# Lipo_Saver.net
KiCad netlist of a schematic drawn in Altium Designer
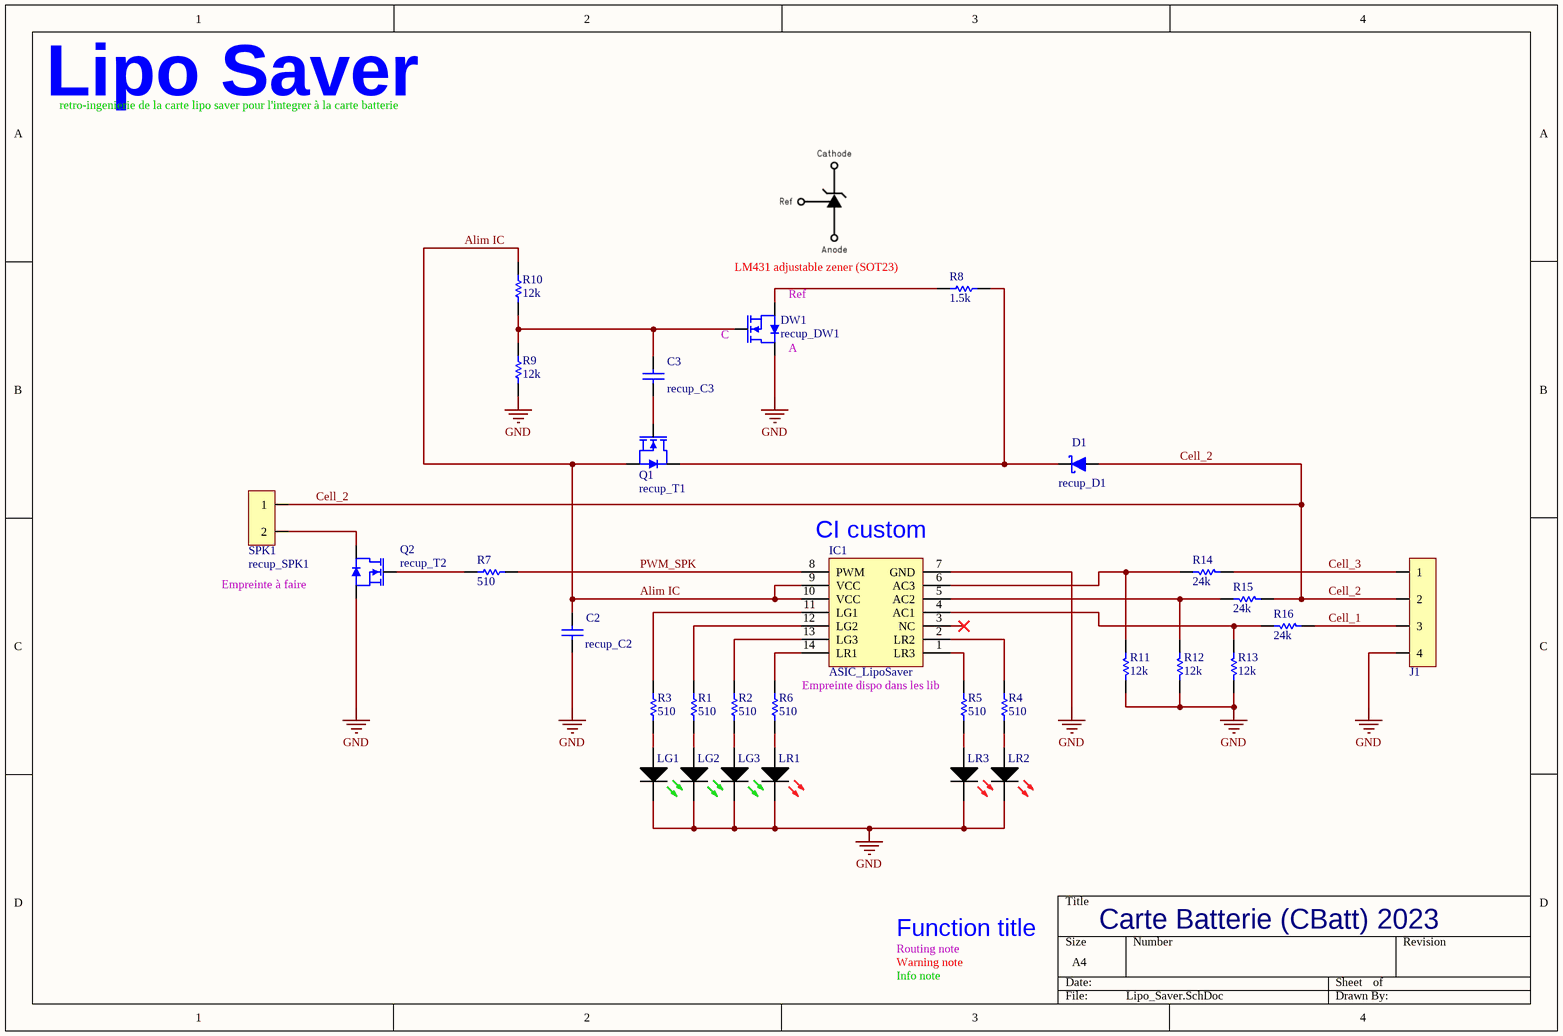
[diagram p0: Lipo_Saver.SchDoc]

(export (version "E")
  (design (tool "Eeschema 10.0.6"))
  (components
    (comp (ref "C2")
      (value "recup_C2")
      (footprint "WCAP-CSGP_0805, 2x1.25x1.25")
      (description "CAP CER 1uF 50V X7R 0805")
      (fields
        (field (name "MANUFACTURER") "Wurth Elektronik")
        (field (name "MANUFACTURER PART NUMBER") "885012207103")
      )
      (libsource (lib "Condensateur") (part "WCAP-CSGP, 885012207103"))
    )
    (comp (ref "C3")
      (value "recup_C3")
      (footprint "WCAP-CSGP_0603, 1.6x0.8x0.8")
      (description "CAP CER 100nF 50V X7R 0603")
      (fields
        (field (name "MANUFACTURER") "Wurth Elektronik")
        (field (name "MANUFACTURER PART NUMBER") "885012206095")
      )
      (libsource (lib "Condensateur") (part "WCAP-CSGP, 885012206095"))
    )
    (comp (ref "D1")
      (value "recup_D1")
      (footprint "SOD-123FL")
      (description "DIODE SCHOTTKY 40V 3A SOD123-FL")
      (fields (field (name "MANUFACTURER") "ROHM") (field (name "MANUFACTURER PART NUMBER") "RBR3MM40ATFTR"))
      (libsource (lib "Diode") (part "RBR3MM40ATFTR"))
    )
    (comp (ref "DW1")
      (value "recup_DW1")
      (footprint "SOT-23")
      (description "MOSFET N 60V 115MA SOT23")
      (fields
        (field (name "MANUFACTURER") "Changjiang Electronics Tech (CJ)")
        (field (name "MANUFACTURER PART NUMBER") "2N7002")
      )
      (libsource (lib "Transistors") (part "2N7002"))
    )
    (comp (ref "IC1")
      (value "ASIC_LipoSaver")
      (footprint "SOIC127P600X175-14N")
      (description "Specific IC for Lipo Saver (extracted")
      (fields (field (name "MANUFACTURER") "LipoSaver"))
      (libsource (lib "CI") (part "ASIC_LipoSaver"))
    )
    (comp (ref "J1")
      (value "22-03-2041")
      (footprint "Conn_22-03-2041")
      (description "CONN HEADER VERT 4POS 2.54MM")
      (fields (field (name "MANUFACTURER") "MOLEX"))
      (libsource (lib "Connecteurs") (part "Conn_22-03-2041"))
    )
    (comp (ref "LG1")
      (value "150060GS75000")
      (footprint "SMCW_0603")
      (description "SMD mono-color Chip LED, WL-SMCW, Green")
      (fields (field (name "MANUFACTURER") "Wurth Elektronik"))
      (libsource (lib "Opto") (part "WL-SMCW 0603  150060GS75000"))
    )
    (comp (ref "LG2")
      (value "150060GS75000")
      (footprint "SMCW_0603")
      (description "SMD mono-color Chip LED, WL-SMCW, Green")
      (fields (field (name "MANUFACTURER") "Wurth Elektronik"))
      (libsource (lib "Opto") (part "WL-SMCW 0603  150060GS75000"))
    )
    (comp (ref "LG3")
      (value "150060GS75000")
      (footprint "SMCW_0603")
      (description "SMD mono-color Chip LED, WL-SMCW, Green")
      (fields (field (name "MANUFACTURER") "Wurth Elektronik"))
      (libsource (lib "Opto") (part "WL-SMCW 0603  150060GS75000"))
    )
    (comp (ref "LR1")
      (value "150060RS75000")
      (footprint "SMCW_0603")
      (description "SMD mono-color Chip LED, WL-SMCW, Red")
      (fields (field (name "MANUFACTURER") "Wurth Elektronik"))
      (libsource (lib "Opto") (part "WL-SMCW 0603  150060RS75000"))
    )
    (comp (ref "LR2")
      (value "150060RS75000")
      (footprint "SMCW_0603")
      (description "SMD mono-color Chip LED, WL-SMCW, Red")
      (fields (field (name "MANUFACTURER") "Wurth Elektronik"))
      (libsource (lib "Opto") (part "WL-SMCW 0603  150060RS75000"))
    )
    (comp (ref "LR3")
      (value "150060RS75000")
      (footprint "SMCW_0603")
      (description "SMD mono-color Chip LED, WL-SMCW, Red")
      (fields (field (name "MANUFACTURER") "Wurth Elektronik"))
      (libsource (lib "Opto") (part "WL-SMCW 0603  150060RS75000"))
    )
    (comp (ref "Q1")
      (value "recup_T1")
      (footprint "SOT-23")
      (description "MOSFET N 60V 115MA SOT23")
      (fields
        (field (name "MANUFACTURER") "Changjiang Electronics Tech (CJ)")
        (field (name "MANUFACTURER PART NUMBER") "2N7002")
      )
      (libsource (lib "Transistors") (part "2N7002"))
    )
    (comp (ref "Q2")
      (value "recup_T2")
      (footprint "SOT-23")
      (description "MOSFET N 60V 115MA SOT23")
      (fields
        (field (name "MANUFACTURER") "Changjiang Electronics Tech (CJ)")
        (field (name "MANUFACTURER PART NUMBER") "2N7002")
      )
      (libsource (lib "Transistors") (part "2N7002"))
    )
    (comp (ref "R1")
      (value "510")
      (footprint "RESC1608X06N")
      (description "RES SMD 100K OHM 1% 1/10W 0603")
      (fields
        (field (name "MANUFACTURER") "Yageo")
        (field (name "MANUFACTURER PART NUMBER") "RC0603FR-07100KL")
      )
      (libsource (lib "Resistance") (part "RC0603FR-07100KL"))
    )
    (comp (ref "R2")
      (value "510")
      (footprint "RESC1608X06N")
      (description "RES SMD 100K OHM 1% 1/10W 0603")
      (fields
        (field (name "MANUFACTURER") "Yageo")
        (field (name "MANUFACTURER PART NUMBER") "RC0603FR-07100KL")
      )
      (libsource (lib "Resistance") (part "RC0603FR-07100KL"))
    )
    (comp (ref "R3")
      (value "510")
      (footprint "RESC1608X06N")
      (description "RES SMD 100K OHM 1% 1/10W 0603")
      (fields
        (field (name "MANUFACTURER") "Yageo")
        (field (name "MANUFACTURER PART NUMBER") "RC0603FR-07100KL")
      )
      (libsource (lib "Resistance") (part "RC0603FR-07100KL"))
    )
    (comp (ref "R4")
      (value "510")
      (footprint "RESC1608X06N")
      (description "RES SMD 100K OHM 1% 1/10W 0603")
      (fields
        (field (name "MANUFACTURER") "Yageo")
        (field (name "MANUFACTURER PART NUMBER") "RC0603FR-07100KL")
      )
      (libsource (lib "Resistance") (part "RC0603FR-07100KL"))
    )
    (comp (ref "R5")
      (value "510")
      (footprint "RESC1608X06N")
      (description "RES SMD 100K OHM 1% 1/10W 0603")
      (fields
        (field (name "MANUFACTURER") "Yageo")
        (field (name "MANUFACTURER PART NUMBER") "RC0603FR-07100KL")
      )
      (libsource (lib "Resistance") (part "RC0603FR-07100KL"))
    )
    (comp (ref "R6")
      (value "510")
      (footprint "RESC1608X06N")
      (description "RES SMD 100K OHM 1% 1/10W 0603")
      (fields
        (field (name "MANUFACTURER") "Yageo")
        (field (name "MANUFACTURER PART NUMBER") "RC0603FR-07100KL")
      )
      (libsource (lib "Resistance") (part "RC0603FR-07100KL"))
    )
    (comp (ref "R7")
      (value "510")
      (footprint "RESC1608X06N")
      (description "RES SMD 100K OHM 1% 1/10W 0603")
      (fields
        (field (name "MANUFACTURER") "Yageo")
        (field (name "MANUFACTURER PART NUMBER") "RC0603FR-07100KL")
      )
      (libsource (lib "Resistance") (part "RC0603FR-07100KL"))
    )
    (comp (ref "R8")
      (value "1.5k")
      (footprint "RESC1608X06N")
      (description "RES SMD 100K OHM 1% 1/10W 0603")
      (fields
        (field (name "MANUFACTURER") "Yageo")
        (field (name "MANUFACTURER PART NUMBER") "RC0603FR-07100KL")
      )
      (libsource (lib "Resistance") (part "RC0603FR-07100KL"))
    )
    (comp (ref "R9")
      (value "12k")
      (footprint "RESC1608X06N")
      (description "RES SMD 100K OHM 1% 1/10W 0603")
      (fields
        (field (name "MANUFACTURER") "Yageo")
        (field (name "MANUFACTURER PART NUMBER") "RC0603FR-07100KL")
      )
      (libsource (lib "Resistance") (part "RC0603FR-07100KL"))
    )
    (comp (ref "R10")
      (value "12k")
      (footprint "RESC1608X06N")
      (description "RES SMD 100K OHM 1% 1/10W 0603")
      (fields
        (field (name "MANUFACTURER") "Yageo")
        (field (name "MANUFACTURER PART NUMBER") "RC0603FR-07100KL")
      )
      (libsource (lib "Resistance") (part "RC0603FR-07100KL"))
    )
    (comp (ref "R11")
      (value "12k")
      (footprint "RESC1608X06N")
      (description "RES SMD 100K OHM 1% 1/10W 0603")
      (fields
        (field (name "MANUFACTURER") "Yageo")
        (field (name "MANUFACTURER PART NUMBER") "RC0603FR-07100KL")
      )
      (libsource (lib "Resistance") (part "RC0603FR-07100KL"))
    )
    (comp (ref "R12")
      (value "12k")
      (footprint "RESC1608X06N")
      (description "RES SMD 100K OHM 1% 1/10W 0603")
      (fields
        (field (name "MANUFACTURER") "Yageo")
        (field (name "MANUFACTURER PART NUMBER") "RC0603FR-07100KL")
      )
      (libsource (lib "Resistance") (part "RC0603FR-07100KL"))
    )
    (comp (ref "R13")
      (value "12k")
      (footprint "RESC1608X06N")
      (description "RES SMD 100K OHM 1% 1/10W 0603")
      (fields
        (field (name "MANUFACTURER") "Yageo")
        (field (name "MANUFACTURER PART NUMBER") "RC0603FR-07100KL")
      )
      (libsource (lib "Resistance") (part "RC0603FR-07100KL"))
    )
    (comp (ref "R14")
      (value "24k")
      (footprint "RESC1608X06N")
      (description "RES SMD 100K OHM 1% 1/10W 0603")
      (fields
        (field (name "MANUFACTURER") "Yageo")
        (field (name "MANUFACTURER PART NUMBER") "RC0603FR-07100KL")
      )
      (libsource (lib "Resistance") (part "RC0603FR-07100KL"))
    )
    (comp (ref "R15")
      (value "24k")
      (footprint "RESC1608X06N")
      (description "RES SMD 100K OHM 1% 1/10W 0603")
      (fields
        (field (name "MANUFACTURER") "Yageo")
        (field (name "MANUFACTURER PART NUMBER") "RC0603FR-07100KL")
      )
      (libsource (lib "Resistance") (part "RC0603FR-07100KL"))
    )
    (comp (ref "R16")
      (value "24k")
      (footprint "RESC1608X06N")
      (description "RES SMD 100K OHM 1% 1/10W 0603")
      (fields
        (field (name "MANUFACTURER") "Yageo")
        (field (name "MANUFACTURER PART NUMBER") "RC0603FR-07100KL")
      )
      (libsource (lib "Resistance") (part "RC0603FR-07100KL"))
    )
    (comp (ref "SPK1")
      (value "recup_SPK1")
      (footprint "22-03-2021")
      (description "CONN HEADER VERT 2POS 2.54MM")
      (fields (field (name "MANUFACTURER PART NUMBER") "22-03-2021") (field (name "MANUFACTURER") "MOLEX"))
      (libsource (lib "Connecteurs") (part "22-03-2021"))
    )
  )
  (nets
    (net (code "1") (name "/Alim IC") (class "Default")
      (node (ref "C2") (pin "2") (pinfunction "2_2") (pintype "passive"))
      (node (ref "IC1") (pin "10") (pinfunction "VCC_10") (pintype "passive"))
      (node (ref "IC1") (pin "9") (pinfunction "VCC_9") (pintype "passive"))
      (node (ref "Q1") (pin "2") (pinfunction "S_2") (pintype "passive"))
      (node (ref "R10") (pin "2") (pinfunction "2_2") (pintype "passive"))
    )
    (net (code "2") (name "/Cell_1") (class "Default")
      (node (ref "J1") (pin "3") (pinfunction "3_3") (pintype "passive"))
      (node (ref "R16") (pin "2") (pinfunction "2_2") (pintype "passive"))
    )
    (net (code "3") (name "/Cell_2") (class "Default")
      (node (ref "D1") (pin "1") (pintype "passive"))
      (node (ref "J1") (pin "2") (pinfunction "2_2") (pintype "passive"))
      (node (ref "R15") (pin "2") (pinfunction "2_2") (pintype "passive"))
      (node (ref "SPK1") (pin "1") (pinfunction "1_1") (pintype "passive"))
    )
    (net (code "4") (name "/Cell_3") (class "Default")
      (node (ref "J1") (pin "1") (pinfunction "1_1") (pintype "passive"))
      (node (ref "R14") (pin "2") (pinfunction "2_2") (pintype "passive"))
    )
    (net (code "5") (name "/PWM_SPK") (class "Default")
      (node (ref "IC1") (pin "8") (pinfunction "PWM_8") (pintype "passive"))
      (node (ref "R7") (pin "1") (pinfunction "1_1") (pintype "passive"))
    )
    (net (code "6") (name "GND") (class "Default")
      (node (ref "C2") (pin "1") (pinfunction "1_1") (pintype "passive"))
      (node (ref "DW1") (pin "3") (pinfunction "D_3") (pintype "passive"))
      (node (ref "IC1") (pin "7") (pinfunction "GND_7") (pintype "passive"))
      (node (ref "J1") (pin "4") (pinfunction "4_4") (pintype "passive"))
      (node (ref "LG1") (pin "1") (pinfunction "C_1") (pintype "passive"))
      (node (ref "LG2") (pin "1") (pinfunction "C_1") (pintype "passive"))
      (node (ref "LG3") (pin "1") (pinfunction "C_1") (pintype "passive"))
      (node (ref "LR1") (pin "1") (pinfunction "C_1") (pintype "passive"))
      (node (ref "LR2") (pin "1") (pinfunction "C_1") (pintype "passive"))
      (node (ref "LR3") (pin "1") (pinfunction "C_1") (pintype "passive"))
      (node (ref "Q2") (pin "2") (pinfunction "S_2") (pintype "passive"))
      (node (ref "R11") (pin "1") (pinfunction "1_1") (pintype "passive"))
      (node (ref "R12") (pin "1") (pinfunction "1_1") (pintype "passive"))
      (node (ref "R13") (pin "1") (pinfunction "1_1") (pintype "passive"))
      (node (ref "R9") (pin "2") (pinfunction "2_2") (pintype "passive"))
    )
    (net (code "7") (name "Net-(DW1-G)") (class "Default")
      (node (ref "C3") (pin "2") (pinfunction "2_2") (pintype "passive"))
      (node (ref "DW1") (pin "1") (pinfunction "G_1") (pintype "passive"))
      (node (ref "R10") (pin "1") (pinfunction "1_1") (pintype "passive"))
      (node (ref "R9") (pin "1") (pinfunction "1_1") (pintype "passive"))
    )
    (net (code "8") (name "Net-(DW1-S)") (class "Default")
      (node (ref "DW1") (pin "2") (pinfunction "S_2") (pintype "passive"))
      (node (ref "R8") (pin "2") (pinfunction "2_2") (pintype "passive"))
    )
    (net (code "9") (name "Net-(IC1-AC1)") (class "Default")
      (node (ref "IC1") (pin "4") (pinfunction "AC1_4") (pintype "passive"))
      (node (ref "R13") (pin "2") (pinfunction "2_2") (pintype "passive"))
      (node (ref "R16") (pin "1") (pinfunction "1_1") (pintype "passive"))
    )
    (net (code "10") (name "Net-(IC1-AC2)") (class "Default")
      (node (ref "IC1") (pin "5") (pinfunction "AC2_5") (pintype "passive"))
      (node (ref "R12") (pin "2") (pinfunction "2_2") (pintype "passive"))
      (node (ref "R15") (pin "1") (pinfunction "1_1") (pintype "passive"))
    )
    (net (code "11") (name "Net-(IC1-AC3)") (class "Default")
      (node (ref "IC1") (pin "6") (pinfunction "AC3_6") (pintype "passive"))
      (node (ref "R11") (pin "2") (pinfunction "2_2") (pintype "passive"))
      (node (ref "R14") (pin "1") (pinfunction "1_1") (pintype "passive"))
    )
    (net (code "12") (name "Net-(IC1-LG1)") (class "Default")
      (node (ref "IC1") (pin "11") (pinfunction "LG1_11") (pintype "passive"))
      (node (ref "R3") (pin "1") (pinfunction "1_1") (pintype "passive"))
    )
    (net (code "13") (name "Net-(IC1-LG2)") (class "Default")
      (node (ref "IC1") (pin "12") (pinfunction "LG2_12") (pintype "passive"))
      (node (ref "R1") (pin "1") (pinfunction "1_1") (pintype "passive"))
    )
    (net (code "14") (name "Net-(IC1-LG3)") (class "Default")
      (node (ref "IC1") (pin "13") (pinfunction "LG3_13") (pintype "passive"))
      (node (ref "R2") (pin "1") (pinfunction "1_1") (pintype "passive"))
    )
    (net (code "15") (name "Net-(IC1-LR1)") (class "Default")
      (node (ref "IC1") (pin "14") (pinfunction "LR1_14") (pintype "passive"))
      (node (ref "R6") (pin "1") (pinfunction "1_1") (pintype "passive"))
    )
    (net (code "16") (name "Net-(IC1-LR2)") (class "Default")
      (node (ref "IC1") (pin "2") (pinfunction "LR2_2") (pintype "passive"))
      (node (ref "R4") (pin "1") (pinfunction "1_1") (pintype "passive"))
    )
    (net (code "17") (name "Net-(IC1-LR3)") (class "Default")
      (node (ref "IC1") (pin "1") (pinfunction "LR3_1") (pintype "passive"))
      (node (ref "R5") (pin "1") (pinfunction "1_1") (pintype "passive"))
    )
    (net (code "18") (name "Net-(LG1-A)") (class "Default")
      (node (ref "LG1") (pin "2") (pinfunction "A_2") (pintype "passive"))
      (node (ref "R3") (pin "2") (pinfunction "2_2") (pintype "passive"))
    )
    (net (code "19") (name "Net-(LG2-A)") (class "Default")
      (node (ref "LG2") (pin "2") (pinfunction "A_2") (pintype "passive"))
      (node (ref "R1") (pin "2") (pinfunction "2_2") (pintype "passive"))
    )
    (net (code "20") (name "Net-(LG3-A)") (class "Default")
      (node (ref "LG3") (pin "2") (pinfunction "A_2") (pintype "passive"))
      (node (ref "R2") (pin "2") (pinfunction "2_2") (pintype "passive"))
    )
    (net (code "21") (name "Net-(LR1-A)") (class "Default")
      (node (ref "LR1") (pin "2") (pinfunction "A_2") (pintype "passive"))
      (node (ref "R6") (pin "2") (pinfunction "2_2") (pintype "passive"))
    )
    (net (code "22") (name "Net-(LR2-A)") (class "Default")
      (node (ref "LR2") (pin "2") (pinfunction "A_2") (pintype "passive"))
      (node (ref "R4") (pin "2") (pinfunction "2_2") (pintype "passive"))
    )
    (net (code "23") (name "Net-(LR3-A)") (class "Default")
      (node (ref "LR3") (pin "2") (pinfunction "A_2") (pintype "passive"))
      (node (ref "R5") (pin "2") (pinfunction "2_2") (pintype "passive"))
    )
    (net (code "24") (name "Net-(Q1-D)") (class "Default")
      (node (ref "D1") (pin "2") (pintype "passive"))
      (node (ref "Q1") (pin "3") (pinfunction "D_3") (pintype "passive"))
      (node (ref "R8") (pin "1") (pinfunction "1_1") (pintype "passive"))
    )
    (net (code "25") (name "Net-(Q1-G)") (class "Default")
      (node (ref "C3") (pin "1") (pinfunction "1_1") (pintype "passive"))
      (node (ref "Q1") (pin "1") (pinfunction "G_1") (pintype "passive"))
    )
    (net (code "26") (name "Net-(Q2-D)") (class "Default")
      (node (ref "Q2") (pin "3") (pinfunction "D_3") (pintype "passive"))
      (node (ref "SPK1") (pin "2") (pinfunction "2_2") (pintype "passive"))
    )
    (net (code "27") (name "Net-(Q2-G)") (class "Default")
      (node (ref "Q2") (pin "1") (pinfunction "G_1") (pintype "passive"))
      (node (ref "R7") (pin "2") (pinfunction "2_2") (pintype "passive"))
    )
    (net (code "28") (name "unconnected-(IC1-NC-Pad3)") (class "Default")
      (node (ref "IC1") (pin "3") (pinfunction "NC_3") (pintype "passive+no_connect"))
    )
  )
)
